# MainPCB.net
KiCad netlist of a schematic drawn in Altium Designer
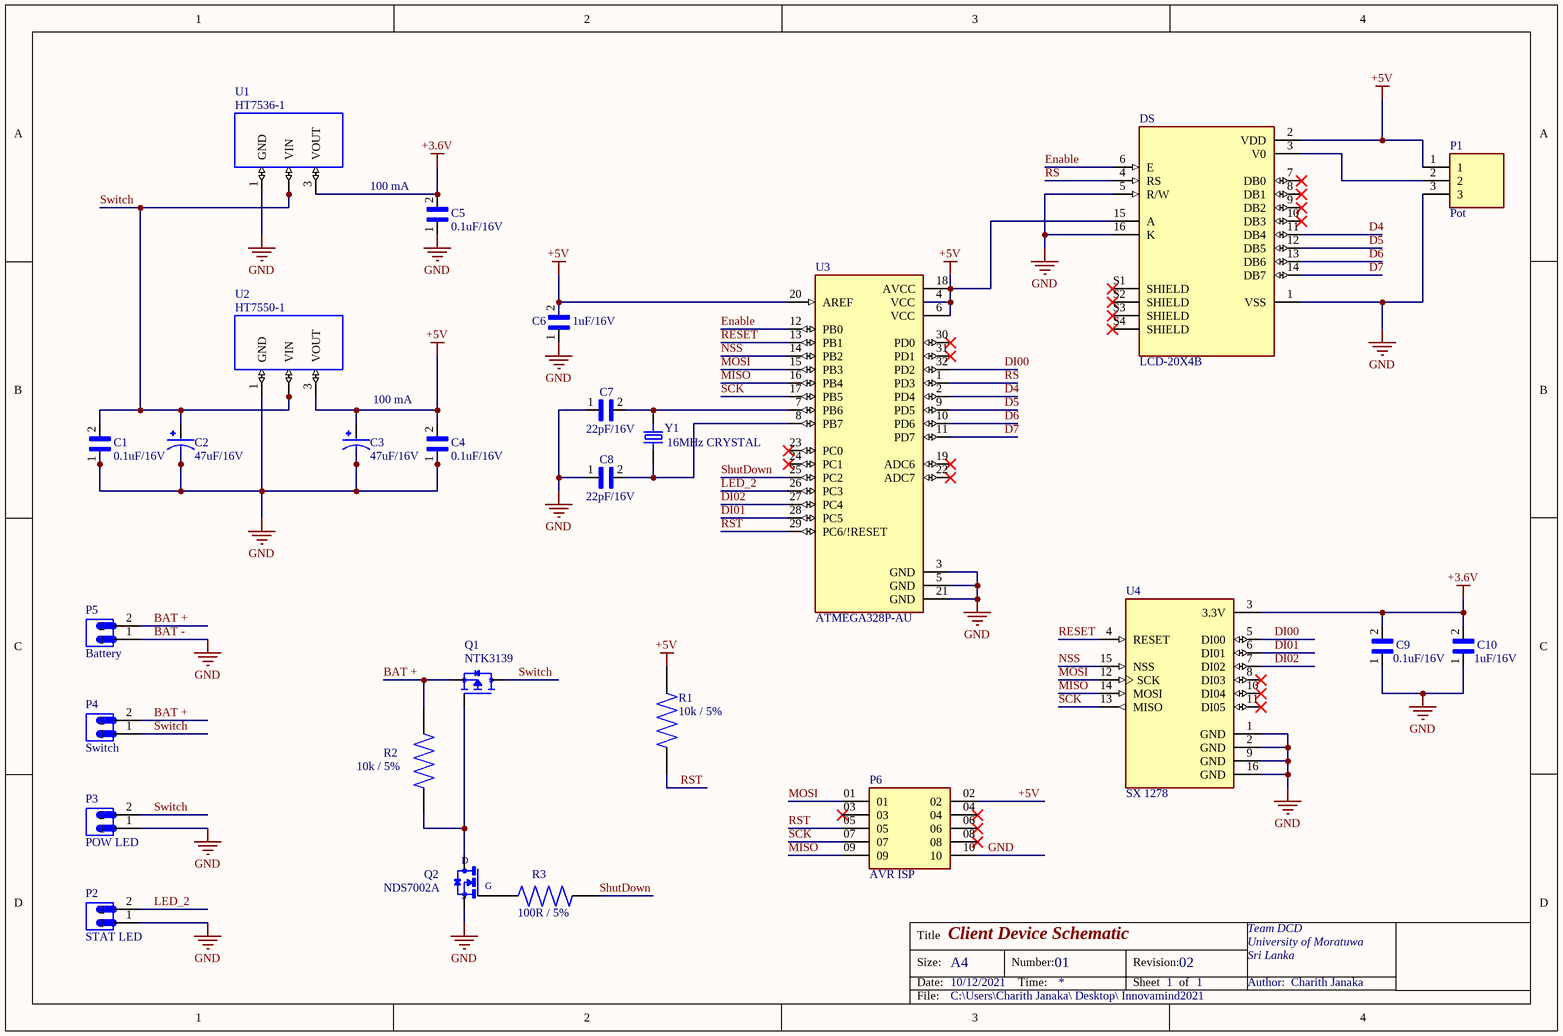
[diagram p0: MainPCB.SchDoc]

(export (version "E")
  (design (tool "Eeschema 10.0.6"))
  (components
    (comp (ref "C1")
      (value "0.1uF/16V")
      (footprint "CAPC3216X110N")
      (fields (field (name "MP") "C1206F104K4RACAUTO"))
      (libsource (lib "C1206F104K4RACAUTO") (part "C1206F104K4RACAUTO"))
    )
    (comp (ref "C2")
      (value "47uF/16V")
      (footprint "CAP_EEEFC0J470AR")
      (description "Cap Aluminum Lytic 47uF 6.3V 20% (5 X 5.4mm) SMD 95mA 1000h 105C Automotive T/R")
      (fields (field (name "MP") "EEEFC0J470AR") (field (name "MF") "Panasonic"))
      (libsource (lib "EEEFC0J470AR") (part "EEEFC0J470AR"))
    )
    (comp (ref "C3")
      (value "47uF/16V")
      (footprint "CAP_EEEFC0J470AR")
      (description "Cap Aluminum Lytic 47uF 6.3V 20% (5 X 5.4mm) SMD 95mA 1000h 105C Automotive T/R")
      (fields (field (name "MP") "EEEFC0J470AR") (field (name "MF") "Panasonic"))
      (libsource (lib "EEEFC0J470AR") (part "EEEFC0J470AR"))
    )
    (comp (ref "C4")
      (value "0.1uF/16V")
      (footprint "CAPC3216X110N")
      (fields (field (name "MP") "C1206F104K4RACAUTO"))
      (libsource (lib "C1206F104K4RACAUTO") (part "C1206F104K4RACAUTO"))
    )
    (comp (ref "C5")
      (value "0.1uF/16V")
      (footprint "CAPC3216X110N")
      (fields (field (name "MP") "C1206F104K4RACAUTO"))
      (libsource (lib "C1206F104K4RACAUTO") (part "C1206F104K4RACAUTO"))
    )
    (comp (ref "C6")
      (value "1uF/16V")
      (footprint "CAPC3316X120N")
      (fields (field (name "MP") "C1206X105J4RECAUTO"))
      (libsource (lib "C1206X105J4RECAUTO") (part "C1206X105J4RECAUTO"))
    )
    (comp (ref "C7")
      (value "22pF/16V")
      (footprint "CAPC3216X88N")
      (fields (field (name "MP") "C1206C220F4HACAUTO"))
      (libsource (lib "C1206C220F4HACAUTO") (part "C1206C220F4HACAUTO"))
    )
    (comp (ref "C8")
      (value "22pF/16V")
      (footprint "CAPC3216X88N")
      (fields (field (name "MP") "C1206C220F4HACAUTO"))
      (libsource (lib "C1206C220F4HACAUTO") (part "C1206C220F4HACAUTO"))
    )
    (comp (ref "C9")
      (value "0.1uF/16V")
      (footprint "CAPC3216X110N")
      (fields (field (name "MP") "C1206F104K4RACAUTO"))
      (libsource (lib "C1206F104K4RACAUTO") (part "C1206F104K4RACAUTO"))
    )
    (comp (ref "C10")
      (value "1uF/16V")
      (footprint "CAPC3316X120N")
      (fields (field (name "MP") "C1206X105J4RECAUTO"))
      (libsource (lib "C1206X105J4RECAUTO") (part "C1206X105J4RECAUTO"))
    )
    (comp (ref "DS")
      (value "LCD-20X4B")
      (footprint "LCD_LCD-20X4B")
      (description "Display Development Tools 20X4 CHARACTER BLUE LCD W/BACKLIGHT")
      (fields (field (name "MF") "Gravitech"))
      (libsource (lib "LCD-20X4B") (part "LCD-20X4B"))
    )
    (comp (ref "P1")
      (value "Pot")
      (footprint "JST_S3B-XH-A(LF)(SN)")
      (description "Connector Header Through Hole, Right Angle 3 position 0.098 _2.50mm_")
      (fields (field (name "MP") "S3B-XH-A_LF__SN_") (field (name "MF") "JST Sales"))
      (libsource (lib "S3B-XH-A_LF__SN_") (part "S3B-XH-A(LF)(SN)"))
    )
    (comp (ref "P2")
      (value "STAT LED")
      (footprint "JST_S2B-XH-A(LF)(SN)")
      (description "Connector Header Through Hole, Right Angle 2 position 0.098 _2.50mm_")
      (fields (field (name "MP") "S2B-XH-A_LF__SN_") (field (name "DIGI-KEY_PART_NUMBER") "455-2257-ND"))
      (libsource (lib "S2B-XH-A_LF__SN_") (part "S2B-XH-A(LF)(SN)"))
    )
    (comp (ref "P3")
      (value "POW LED")
      (footprint "JST_S2B-XH-A(LF)(SN)")
      (description "Connector Header Through Hole, Right Angle 2 position 0.098 _2.50mm_")
      (fields (field (name "MP") "S2B-XH-A_LF__SN_") (field (name "DIGI-KEY_PART_NUMBER") "455-2257-ND"))
      (libsource (lib "S2B-XH-A_LF__SN_") (part "S2B-XH-A(LF)(SN)"))
    )
    (comp (ref "P4")
      (value "Switch")
      (footprint "JST_S2B-XH-A(LF)(SN)")
      (description "Connector Header Through Hole, Right Angle 2 position 0.098 _2.50mm_")
      (fields (field (name "MP") "S2B-XH-A_LF__SN_") (field (name "DIGI-KEY_PART_NUMBER") "455-2257-ND"))
      (libsource (lib "S2B-XH-A_LF__SN_") (part "S2B-XH-A(LF)(SN)"))
    )
    (comp (ref "P5")
      (value "Battery")
      (footprint "JST_S2B-XH-A(LF)(SN)")
      (description "Connector Header Through Hole, Right Angle 2 position 0.098 _2.50mm_")
      (fields (field (name "MP") "S2B-XH-A_LF__SN_") (field (name "DIGI-KEY_PART_NUMBER") "455-2257-ND"))
      (libsource (lib "S2B-XH-A_LF__SN_") (part "S2B-XH-A(LF)(SN)"))
    )
    (comp (ref "P6")
      (value "AVR ISP")
      (footprint "SAMTEC_TSW-105-05-L-D")
      (fields (field (name "MP") "TSW-105-05-L-D"))
      (libsource (lib "TSW-105-05-L-D") (part "TSW-105-05-L-D"))
    )
    (comp (ref "Q1")
      (value "NTK3139")
      (footprint "SOT40P120X55-3N")
      (description "P-Channel 20V 660mA (Ta) 310mW (Ta) Surface Mount SOT-723")
      (fields (field (name "MF") "ON Semiconductor") (field (name "MP") "NTK3139PT1G"))
      (libsource (lib "NTK3139PT1G") (part "NTK3139PT1G"))
    )
    (comp (ref "Q2")
      (value "NDS7002A")
      (footprint "SOT23")
      (description "N-Channel 60V 280mA _Ta_ 300mW _Ta_ Surface Mount SOT-23 _TO-236AB_")
      (fields (field (name "MF") "ON Semiconductor"))
      (libsource (lib "NDS7002A") (part "NDS7002A"))
    )
    (comp (ref "R1")
      (value "10k / 5%")
      (footprint "RESC3115X65N")
      (fields (field (name "MF") "TE Connectivity") (field (name "MP") "CRGCQ1206J10K"))
      (libsource (lib "CRGCQ1206J10K") (part "CRGCQ1206J10K"))
    )
    (comp (ref "R2")
      (value "10k / 5%")
      (footprint "RESC3115X65N")
      (description "Fixed Resistor CRGCQ 1206 10K 5%")
      (fields (field (name "MF") "TE Connectivity") (field (name "MP") "CRGCQ1206J10K"))
      (libsource (lib "CRGCQ1206J10K") (part "CRGCQ1206J10K"))
    )
    (comp (ref "R3")
      (value "100R / 5%")
      (footprint "RESC3115X65N")
      (description "Fixed Resistor CRGCQ 1206 100R 5%")
      (fields (field (name "MP") "CRGCQ1206J100R"))
      (libsource (lib "CRGCQ1206J100R") (part "CRGCQ1206J100R"))
    )
    (comp (ref "U1")
      (value "HT7536-1")
      (footprint "SOT89")
      (description "Voltage stabiliser; LDO, fixed; 5V; 0.1A; SOT89; SMD")
      (fields (field (name "MP") "HT7550-1") (field (name "MF") "Holtek"))
      (libsource (lib "HT7550-1") (part "HT7550-1"))
    )
    (comp (ref "U2")
      (value "HT7550-1")
      (footprint "SOT89")
      (description "Voltage stabiliser; LDO, fixed; 5V; 0.1A; SOT89; SMD")
      (fields (field (name "MF") "Holtek"))
      (libsource (lib "HT7550-1") (part "HT7550-1"))
    )
    (comp (ref "U3")
      (value "ATMEGA328P-AU")
      (footprint "QFP80P900X900X120-32N")
      (description "AVR AVRÂ® ATmega Microcontroller IC 8-Bit 20MHz 32KB _16K x 16_ FLASH 32-TQFP _7x7_")
      (fields (field (name "MF") "Microchip"))
      (libsource (lib "ATMEGA328P-AU") (part "ATMEGA328P-AU"))
    )
    (comp (ref "U4")
      (value "SX 1278")
      (footprint "MODULE_RA-02_LORA")
      (description "Ra-02 LoRa RF M5Stack Platform Evaluation Expansion Board")
      (fields (field (name "MP") "Ra-02 LoRa") (field (name "MF") "AI-Thinker"))
      (libsource (lib "RA-02_LORA") (part "RA-02_LORA"))
    )
    (comp (ref "Y1")
      (value "16MHz CRYSTAL")
      (footprint "XTAL_ECS-160-20-5PVX")
      (description "16MHz Â±30ppm Crystal 20pF 50 Ohms HC-49/US")
      (fields (field (name "MF") "ECS Inc.") (field (name "MP") "ECS-160-20-5PVX"))
      (libsource (lib "ECS-160-20-5PVX") (part "ECS-160-20-5PVX"))
    )
  )
  (nets
    (net (code "1") (name "+3.6V") (class "Default")
      (node (ref "C10") (pin "2") (pinfunction "2_2") (pintype "passive"))
      (node (ref "C5") (pin "2") (pinfunction "2_2") (pintype "passive"))
      (node (ref "C9") (pin "2") (pinfunction "2_2") (pintype "passive"))
      (node (ref "U1") (pin "3") (pinfunction "VOUT_3") (pintype "bidirectional"))
      (node (ref "U4") (pin "3") (pinfunction "3.3V_3") (pintype "power_in"))
    )
    (net (code "2") (name "+5V") (class "Default")
      (node (ref "C3") (pin "1") (pinfunction "1_1") (pintype "passive"))
      (node (ref "C4") (pin "2") (pinfunction "2_2") (pintype "passive"))
      (node (ref "C6") (pin "2") (pinfunction "2_2") (pintype "passive"))
      (node (ref "DS") (pin "15") (pinfunction "A_15") (pintype "passive"))
      (node (ref "DS") (pin "2") (pinfunction "VDD_2") (pintype "power_in"))
      (node (ref "P1") (pin "1") (pinfunction "1_1") (pintype "passive"))
      (node (ref "P6") (pin "02") (pinfunction "02_02") (pintype "passive"))
      (node (ref "R1") (pin "1") (pinfunction "1_1") (pintype "passive"))
      (node (ref "U2") (pin "3") (pinfunction "VOUT_3") (pintype "bidirectional"))
      (node (ref "U3") (pin "18") (pinfunction "AVCC_18") (pintype "power_in"))
      (node (ref "U3") (pin "20") (pinfunction "AREF_20") (pintype "input"))
      (node (ref "U3") (pin "4") (pinfunction "VCC_4") (pintype "power_in"))
      (node (ref "U3") (pin "6") (pinfunction "VCC_6") (pintype "power_in"))
    )
    (net (code "3") (name "/BAT +") (class "Default")
      (node (ref "P4") (pin "2") (pinfunction "2_2") (pintype "passive"))
      (node (ref "P5") (pin "2") (pinfunction "2_2") (pintype "passive"))
      (node (ref "Q1") (pin "2") (pinfunction "S_2") (pintype "passive"))
      (node (ref "R2") (pin "2") (pinfunction "2_2") (pintype "passive"))
    )
    (net (code "4") (name "/D4") (class "Default")
      (node (ref "DS") (pin "11") (pinfunction "DB4_11") (pintype "bidirectional"))
      (node (ref "U3") (pin "2") (pinfunction "PD4_2") (pintype "bidirectional"))
    )
    (net (code "5") (name "/D5") (class "Default")
      (node (ref "DS") (pin "12") (pinfunction "DB5_12") (pintype "bidirectional"))
      (node (ref "U3") (pin "9") (pinfunction "PD5_9") (pintype "bidirectional"))
    )
    (net (code "6") (name "/D6") (class "Default")
      (node (ref "DS") (pin "13") (pinfunction "DB6_13") (pintype "bidirectional"))
      (node (ref "U3") (pin "10") (pinfunction "PD6_10") (pintype "bidirectional"))
    )
    (net (code "7") (name "/D7") (class "Default")
      (node (ref "DS") (pin "14") (pinfunction "DB7_14") (pintype "bidirectional"))
      (node (ref "U3") (pin "11") (pinfunction "PD7_11") (pintype "bidirectional"))
    )
    (net (code "8") (name "/DI00") (class "Default")
      (node (ref "U3") (pin "32") (pinfunction "PD2_32") (pintype "bidirectional"))
      (node (ref "U4") (pin "5") (pinfunction "DI00_5") (pintype "bidirectional"))
    )
    (net (code "9") (name "/DI01") (class "Default")
      (node (ref "U3") (pin "28") (pinfunction "PC5_28") (pintype "bidirectional"))
      (node (ref "U4") (pin "6") (pinfunction "DI01_6") (pintype "bidirectional"))
    )
    (net (code "10") (name "/DI02") (class "Default")
      (node (ref "U3") (pin "27") (pinfunction "PC4_27") (pintype "bidirectional"))
      (node (ref "U4") (pin "7") (pinfunction "DI02_7") (pintype "bidirectional"))
    )
    (net (code "11") (name "/Enable") (class "Default")
      (node (ref "DS") (pin "6") (pinfunction "E_6") (pintype "input"))
      (node (ref "U3") (pin "12") (pinfunction "PB0_12") (pintype "bidirectional"))
    )
    (net (code "12") (name "/LED_2") (class "Default")
      (node (ref "P2") (pin "2") (pinfunction "2_2") (pintype "passive"))
      (node (ref "U3") (pin "26") (pinfunction "PC3_26") (pintype "bidirectional"))
    )
    (net (code "13") (name "/MISO") (class "Default")
      (node (ref "P6") (pin "09") (pinfunction "09_09") (pintype "passive"))
      (node (ref "U3") (pin "16") (pinfunction "PB4_16") (pintype "bidirectional"))
      (node (ref "U4") (pin "14") (pinfunction "MOSI_14") (pintype "input"))
    )
    (net (code "14") (name "/MOSI") (class "Default")
      (node (ref "P6") (pin "01") (pinfunction "01_01") (pintype "passive"))
      (node (ref "U3") (pin "15") (pinfunction "PB3_15") (pintype "bidirectional"))
      (node (ref "U4") (pin "12") (pinfunction "SCK_12") (pintype "input"))
    )
    (net (code "15") (name "/NSS") (class "Default")
      (node (ref "U3") (pin "14") (pinfunction "PB2_14") (pintype "bidirectional"))
      (node (ref "U4") (pin "15") (pinfunction "NSS_15") (pintype "input"))
    )
    (net (code "16") (name "/RESET") (class "Default")
      (node (ref "U3") (pin "13") (pinfunction "PB1_13") (pintype "bidirectional"))
      (node (ref "U4") (pin "4") (pinfunction "RESET_4") (pintype "input"))
    )
    (net (code "17") (name "/RS") (class "Default")
      (node (ref "DS") (pin "4") (pinfunction "RS_4") (pintype "input"))
      (node (ref "U3") (pin "1") (pinfunction "PD3_1") (pintype "bidirectional"))
    )
    (net (code "18") (name "/RST") (class "Default")
      (node (ref "P6") (pin "05") (pinfunction "05_05") (pintype "passive"))
      (node (ref "R1") (pin "2") (pinfunction "2_2") (pintype "passive"))
      (node (ref "U3") (pin "29") (pinfunction "PC6/!RESET_29") (pintype "bidirectional"))
    )
    (net (code "19") (name "/SCK") (class "Default")
      (node (ref "P6") (pin "07") (pinfunction "07_07") (pintype "passive"))
      (node (ref "U3") (pin "17") (pinfunction "PB5_17") (pintype "bidirectional"))
      (node (ref "U4") (pin "13") (pinfunction "MISO_13") (pintype "output"))
    )
    (net (code "20") (name "/ShutDown") (class "Default")
      (node (ref "R3") (pin "2") (pinfunction "2_2") (pintype "passive"))
      (node (ref "U3") (pin "25") (pinfunction "PC2_25") (pintype "bidirectional"))
    )
    (net (code "21") (name "/Switch") (class "Default")
      (node (ref "C1") (pin "2") (pinfunction "2_2") (pintype "passive"))
      (node (ref "C2") (pin "1") (pinfunction "1_1") (pintype "passive"))
      (node (ref "P3") (pin "2") (pinfunction "2_2") (pintype "passive"))
      (node (ref "P4") (pin "1") (pinfunction "1_1") (pintype "passive"))
      (node (ref "Q1") (pin "3") (pinfunction "D_3") (pintype "passive"))
      (node (ref "U1") (pin "2") (pinfunction "VIN_2") (pintype "bidirectional"))
      (node (ref "U1") (pin "2@1") (pinfunction "VIN_2@1") (pintype "bidirectional"))
      (node (ref "U2") (pin "2") (pinfunction "VIN_2") (pintype "bidirectional"))
      (node (ref "U2") (pin "2@1") (pinfunction "VIN_2@1") (pintype "bidirectional"))
    )
    (net (code "22") (name "GND") (class "Default")
      (node (ref "C1") (pin "1") (pinfunction "1_1") (pintype "passive"))
      (node (ref "C10") (pin "1") (pinfunction "1_1") (pintype "passive"))
      (node (ref "C2") (pin "2") (pinfunction "2_2") (pintype "passive"))
      (node (ref "C3") (pin "2") (pinfunction "2_2") (pintype "passive"))
      (node (ref "C4") (pin "1") (pinfunction "1_1") (pintype "passive"))
      (node (ref "C5") (pin "1") (pinfunction "1_1") (pintype "passive"))
      (node (ref "C6") (pin "1") (pinfunction "1_1") (pintype "passive"))
      (node (ref "C7") (pin "1") (pinfunction "1_1") (pintype "passive"))
      (node (ref "C8") (pin "1") (pinfunction "1_1") (pintype "passive"))
      (node (ref "C9") (pin "1") (pinfunction "1_1") (pintype "passive"))
      (node (ref "DS") (pin "1") (pinfunction "VSS_1") (pintype "power_in"))
      (node (ref "DS") (pin "16") (pinfunction "K_16") (pintype "passive"))
      (node (ref "DS") (pin "5") (pinfunction "R/W_5") (pintype "input"))
      (node (ref "P1") (pin "3") (pinfunction "3_3") (pintype "passive"))
      (node (ref "P2") (pin "1") (pinfunction "1_1") (pintype "passive"))
      (node (ref "P3") (pin "1") (pinfunction "1_1") (pintype "passive"))
      (node (ref "P5") (pin "1") (pinfunction "1_1") (pintype "passive"))
      (node (ref "P6") (pin "10") (pinfunction "10_10") (pintype "passive"))
      (node (ref "Q2") (pin "2") (pinfunction "S_2") (pintype "passive"))
      (node (ref "U1") (pin "1") (pinfunction "GND_1") (pintype "bidirectional"))
      (node (ref "U2") (pin "1") (pinfunction "GND_1") (pintype "bidirectional"))
      (node (ref "U3") (pin "21") (pinfunction "GND_21") (pintype "power_in"))
      (node (ref "U3") (pin "3") (pinfunction "GND_3") (pintype "power_in"))
      (node (ref "U3") (pin "5") (pinfunction "GND_5") (pintype "power_in"))
      (node (ref "U4") (pin "1") (pinfunction "GND_1") (pintype "power_in"))
      (node (ref "U4") (pin "16") (pinfunction "GND_16") (pintype "power_in"))
      (node (ref "U4") (pin "2") (pinfunction "GND_2") (pintype "power_in"))
      (node (ref "U4") (pin "9") (pinfunction "GND_9") (pintype "power_in"))
    )
    (net (code "23") (name "Net-(DS-V0)") (class "Default")
      (node (ref "DS") (pin "3") (pinfunction "V0_3") (pintype "power_in"))
      (node (ref "P1") (pin "2") (pinfunction "2_2") (pintype "passive"))
    )
    (net (code "24") (name "Net-(Q1-G)") (class "Default")
      (node (ref "Q1") (pin "1") (pinfunction "G_1") (pintype "passive"))
      (node (ref "Q2") (pin "3") (pinfunction "D_3") (pintype "passive"))
      (node (ref "R2") (pin "1") (pinfunction "1_1") (pintype "passive"))
    )
    (net (code "25") (name "Net-(Q2-G)") (class "Default")
      (node (ref "Q2") (pin "1") (pinfunction "G_1") (pintype "passive"))
      (node (ref "R3") (pin "1") (pinfunction "1_1") (pintype "passive"))
    )
    (net (code "26") (name "Net-(U3-PB6)") (class "Default")
      (node (ref "C7") (pin "2") (pinfunction "2_2") (pintype "passive"))
      (node (ref "U3") (pin "7") (pinfunction "PB6_7") (pintype "bidirectional"))
      (node (ref "Y1") (pin "2") (pinfunction "2_2") (pintype "passive"))
    )
    (net (code "27") (name "Net-(U3-PB7)") (class "Default")
      (node (ref "C8") (pin "2") (pinfunction "2_2") (pintype "passive"))
      (node (ref "U3") (pin "8") (pinfunction "PB7_8") (pintype "bidirectional"))
      (node (ref "Y1") (pin "1") (pinfunction "1_1") (pintype "passive"))
    )
    (net (code "28") (name "unconnected-(DS-DB0-Pad7)") (class "Default")
      (node (ref "DS") (pin "7") (pinfunction "DB0_7") (pintype "bidirectional+no_connect"))
    )
    (net (code "29") (name "unconnected-(DS-DB1-Pad8)") (class "Default")
      (node (ref "DS") (pin "8") (pinfunction "DB1_8") (pintype "bidirectional+no_connect"))
    )
    (net (code "30") (name "unconnected-(DS-DB2-Pad9)") (class "Default")
      (node (ref "DS") (pin "9") (pinfunction "DB2_9") (pintype "bidirectional+no_connect"))
    )
    (net (code "31") (name "unconnected-(DS-DB3-Pad10)") (class "Default")
      (node (ref "DS") (pin "10") (pinfunction "DB3_10") (pintype "bidirectional+no_connect"))
    )
    (net (code "32") (name "unconnected-(DS-SHIELD-PadS1)") (class "Default")
      (node (ref "DS") (pin "S1") (pinfunction "SHIELD_S1") (pintype "passive+no_connect"))
    )
    (net (code "33") (name "unconnected-(DS-SHIELD-PadS2)") (class "Default")
      (node (ref "DS") (pin "S2") (pinfunction "SHIELD_S2") (pintype "passive+no_connect"))
    )
    (net (code "34") (name "unconnected-(DS-SHIELD-PadS3)") (class "Default")
      (node (ref "DS") (pin "S3") (pinfunction "SHIELD_S3") (pintype "passive+no_connect"))
    )
    (net (code "35") (name "unconnected-(DS-SHIELD-PadS4)") (class "Default")
      (node (ref "DS") (pin "S4") (pinfunction "SHIELD_S4") (pintype "passive+no_connect"))
    )
    (net (code "36") (name "unconnected-(P6-Pad03)") (class "Default")
      (node (ref "P6") (pin "03") (pinfunction "03_03") (pintype "passive+no_connect"))
    )
    (net (code "37") (name "unconnected-(P6-Pad04)") (class "Default")
      (node (ref "P6") (pin "04") (pinfunction "04_04") (pintype "passive+no_connect"))
    )
    (net (code "38") (name "unconnected-(P6-Pad06)") (class "Default")
      (node (ref "P6") (pin "06") (pinfunction "06_06") (pintype "passive+no_connect"))
    )
    (net (code "39") (name "unconnected-(P6-Pad08)") (class "Default")
      (node (ref "P6") (pin "08") (pinfunction "08_08") (pintype "passive+no_connect"))
    )
    (net (code "40") (name "unconnected-(U3-ADC6-Pad19)") (class "Default")
      (node (ref "U3") (pin "19") (pinfunction "ADC6_19") (pintype "bidirectional+no_connect"))
    )
    (net (code "41") (name "unconnected-(U3-ADC7-Pad22)") (class "Default")
      (node (ref "U3") (pin "22") (pinfunction "ADC7_22") (pintype "bidirectional+no_connect"))
    )
    (net (code "42") (name "unconnected-(U3-PC0-Pad23)") (class "Default")
      (node (ref "U3") (pin "23") (pinfunction "PC0_23") (pintype "bidirectional+no_connect"))
    )
    (net (code "43") (name "unconnected-(U3-PC1-Pad24)") (class "Default")
      (node (ref "U3") (pin "24") (pinfunction "PC1_24") (pintype "bidirectional+no_connect"))
    )
    (net (code "44") (name "unconnected-(U3-PD0-Pad30)") (class "Default")
      (node (ref "U3") (pin "30") (pinfunction "PD0_30") (pintype "bidirectional+no_connect"))
    )
    (net (code "45") (name "unconnected-(U3-PD1-Pad31)") (class "Default")
      (node (ref "U3") (pin "31") (pinfunction "PD1_31") (pintype "bidirectional+no_connect"))
    )
    (net (code "46") (name "unconnected-(U4-DI03-Pad8)") (class "Default")
      (node (ref "U4") (pin "8") (pinfunction "DI03_8") (pintype "bidirectional+no_connect"))
    )
    (net (code "47") (name "unconnected-(U4-DI04-Pad10)") (class "Default")
      (node (ref "U4") (pin "10") (pinfunction "DI04_10") (pintype "bidirectional+no_connect"))
    )
    (net (code "48") (name "unconnected-(U4-DI05-Pad11)") (class "Default")
      (node (ref "U4") (pin "11") (pinfunction "DI05_11") (pintype "bidirectional+no_connect"))
    )
  )
)
